# cheap_load_share_v2.net
KiCad netlist of a schematic drawn in EAGLE
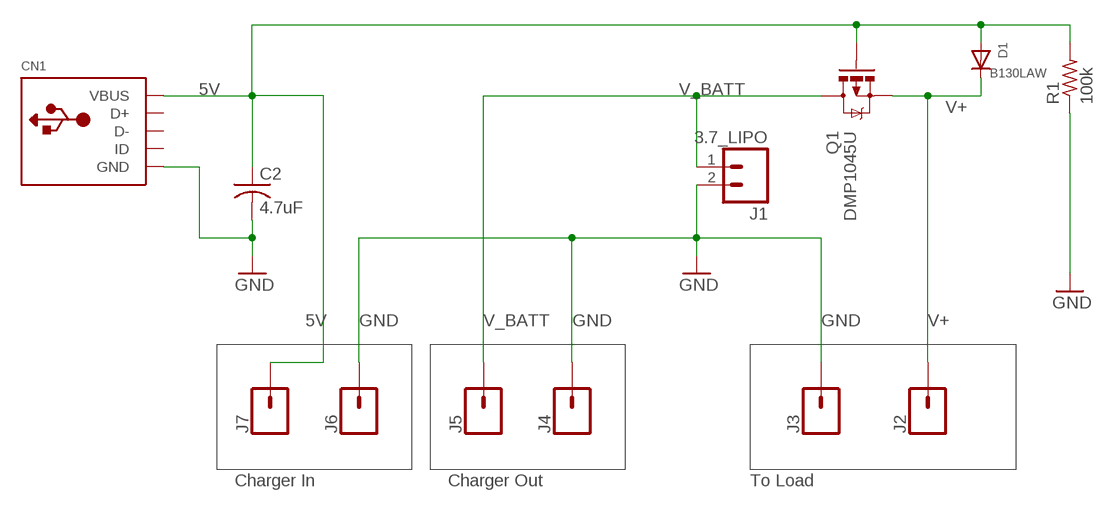
[diagram p0: schematic, sheet 1]

(export (version "E")
  (design (tool "Eeschema 10.0.6"))
  (components
    (comp (ref "C2")
      (value "4.7uF")
      (footprint "eagle-import:C0402K")
      (libsource (lib "eagle-import") (part "C-USC0402K"))
    )
    (comp (ref "CN1")
      (value "USBMINIB")
      (footprint "eagle-import:USB-MINIB")
      (libsource (lib "eagle-import") (part "USBMINIB"))
    )
    (comp (ref "D1")
      (value "B130LAW")
      (footprint "eagle-import:SOD-123")
      (libsource (lib "eagle-import") (part "DIODESOD-123"))
    )
    (comp (ref "J1")
      (value "3.7_LIPO")
      (footprint "eagle-import:1X02")
      (libsource (lib "eagle-import") (part "M02PTH"))
    )
    (comp (ref "J2")
      (value "CONN_01OFFSET")
      (footprint "eagle-import:1X01_OFFSET")
      (libsource (lib "eagle-import") (part "CONN_01OFFSET"))
    )
    (comp (ref "J3")
      (value "CONN_01OFFSET")
      (footprint "eagle-import:1X01_OFFSET")
      (libsource (lib "eagle-import") (part "CONN_01OFFSET"))
    )
    (comp (ref "J4")
      (value "CONN_01OFFSET")
      (footprint "eagle-import:1X01_OFFSET")
      (libsource (lib "eagle-import") (part "CONN_01OFFSET"))
    )
    (comp (ref "J5")
      (value "CONN_01OFFSET")
      (footprint "eagle-import:1X01_OFFSET")
      (libsource (lib "eagle-import") (part "CONN_01OFFSET"))
    )
    (comp (ref "J6")
      (value "CONN_01OFFSET")
      (footprint "eagle-import:1X01_OFFSET")
      (libsource (lib "eagle-import") (part "CONN_01OFFSET"))
    )
    (comp (ref "J7")
      (value "CONN_01OFFSET")
      (footprint "eagle-import:1X01_OFFSET")
      (libsource (lib "eagle-import") (part "CONN_01OFFSET"))
    )
    (comp (ref "Q1")
      (value "DMP1045U")
      (footprint "eagle-import:SOT23-3")
      (libsource (lib "eagle-import") (part "MOSFET-PCHANNEL"))
    )
    (comp (ref "R1")
      (value "100k")
      (footprint "eagle-import:R0805W")
      (libsource (lib "eagle-import") (part "R-US_R0805W"))
    )
  )
  (nets
    (net (code "1") (name "/5V") (class "Default")
      (node (ref "C2") (pin "1") (pinfunction "1_1") (pintype "passive"))
      (node (ref "CN1") (pin "VBUS") (pinfunction "VBUS_VBUS") (pintype "power_in"))
      (node (ref "D1") (pin "A") (pinfunction "A_A") (pintype "passive"))
      (node (ref "J7") (pin "1") (pinfunction "1_1") (pintype "passive"))
      (node (ref "Q1") (pin "1") (pinfunction "G_1") (pintype "passive"))
      (node (ref "R1") (pin "2") (pinfunction "2_2") (pintype "passive"))
    )
    (net (code "2") (name "/V+") (class "Default")
      (node (ref "D1") (pin "C") (pinfunction "C_C") (pintype "passive"))
      (node (ref "J2") (pin "1") (pinfunction "1_1") (pintype "passive"))
      (node (ref "Q1") (pin "2") (pinfunction "S_2") (pintype "passive"))
    )
    (net (code "3") (name "/V_BATT") (class "Default")
      (node (ref "J1") (pin "1") (pinfunction "1_1") (pintype "passive"))
      (node (ref "J5") (pin "1") (pinfunction "1_1") (pintype "passive"))
      (node (ref "Q1") (pin "3") (pinfunction "D_3") (pintype "passive"))
    )
    (net (code "4") (name "GND") (class "Default")
      (node (ref "C2") (pin "2") (pinfunction "2_2") (pintype "passive"))
      (node (ref "CN1") (pin "GND") (pinfunction "GND_GND") (pintype "power_in"))
      (node (ref "CN1") (pin "GND1") (pinfunction "GND_GND1") (pintype "power_in"))
      (node (ref "CN1") (pin "GND2") (pinfunction "GND_GND2") (pintype "power_in"))
      (node (ref "CN1") (pin "GND3") (pinfunction "GND_GND3") (pintype "power_in"))
      (node (ref "CN1") (pin "GND4") (pinfunction "GND_GND4") (pintype "power_in"))
      (node (ref "J1") (pin "2") (pinfunction "2_2") (pintype "passive"))
      (node (ref "J3") (pin "1") (pinfunction "1_1") (pintype "passive"))
      (node (ref "J4") (pin "1") (pinfunction "1_1") (pintype "passive"))
      (node (ref "J6") (pin "1") (pinfunction "1_1") (pintype "passive"))
      (node (ref "R1") (pin "1") (pinfunction "1_1") (pintype "passive"))
    )
    (net (code "5") (name "unconnected-(CN1-PadD+)") (class "Default")
      (node (ref "CN1") (pin "D+") (pinfunction "D+_D+") (pintype "bidirectional"))
    )
    (net (code "6") (name "unconnected-(CN1-PadD-)") (class "Default")
      (node (ref "CN1") (pin "D-") (pinfunction "D-_D-") (pintype "bidirectional"))
    )
    (net (code "7") (name "unconnected-(CN1-PadID)") (class "Default")
      (node (ref "CN1") (pin "ID") (pinfunction "ID_ID") (pintype "bidirectional"))
    )
  )
)
